# EC3micro.net
KiCad netlist of a schematic drawn in Altium Designer
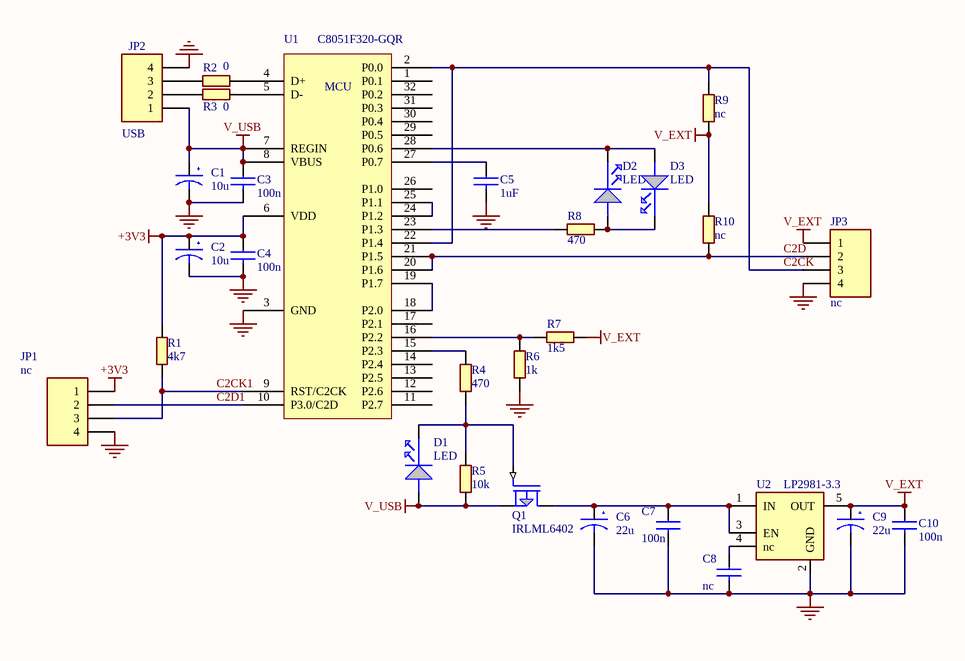
[diagram p0: EC3micro.SchDoc]

(export (version "E")
  (design (tool "Eeschema 10.0.6"))
  (components
    (comp (ref "C1") (value "10u") (footprint "TANTAL-A") (libsource (lib "RCS-Discret") (part "C-EL-TAN")))
    (comp (ref "C2") (value "10u") (footprint "TANTAL-A") (libsource (lib "RCS-Discret") (part "C-EL-TAN")))
    (comp (ref "C3") (value "100n") (footprint "C-0603") (libsource (lib "RCS-Discret") (part "C")))
    (comp (ref "C4") (value "100n") (footprint "C-0603") (libsource (lib "RCS-Discret") (part "C")))
    (comp (ref "C5") (value "1uF") (footprint "C-0805") (libsource (lib "RCS-Discret") (part "C")))
    (comp (ref "C6") (value "22u") (footprint "TANTAL-A") (libsource (lib "RCS-Discret") (part "C-EL-TAN")))
    (comp (ref "C7") (value "100n") (footprint "C-0603") (libsource (lib "RCS-Discret") (part "C")))
    (comp (ref "C8") (value "nc") (footprint "C-0603") (libsource (lib "RCS-Discret") (part "C")))
    (comp (ref "C9") (value "22u") (footprint "TANTAL-A") (libsource (lib "RCS-Discret") (part "C-EL-TAN")))
    (comp (ref "C10") (value "100n") (footprint "C-0603") (libsource (lib "RCS-Discret") (part "C")))
    (comp (ref "D1") (value "LED") (footprint "LED-0805") (libsource (lib "RCS-Discret") (part "LED")))
    (comp (ref "D2") (value "LED") (footprint "LED-0805") (libsource (lib "RCS-Discret") (part "LED")))
    (comp (ref "D3") (value "LED") (footprint "LED-0805") (libsource (lib "RCS-Discret") (part "LED")))
    (comp (ref "JP1")
      (value "nc")
      (footprint "IDS1-4P")
      (description "4 Pin Header 2,0 mm, 1x04")
      (libsource (lib "") (part "HEADER 4_1"))
    )
    (comp (ref "JP2")
      (value "USB")
      (footprint "CONN4_long")
      (description "4 Pin Header 2,0 mm, 1x04")
      (libsource (lib "e4") (part "HEADER 4"))
    )
    (comp (ref "JP3")
      (value "nc")
      (footprint "CONN4_long")
      (description "4 Pin Header 2,0 mm, 1x04")
      (libsource (lib "") (part "HEADER 4_2"))
    )
    (comp (ref "Q1")
      (value "IRLML6402")
      (footprint "SOT-23")
      (libsource (lib "RCS-Discret") (part "IRLML6402"))
    )
    (comp (ref "R1") (value "4k7") (footprint "R-0603") (libsource (lib "") (part "RES_1")))
    (comp (ref "R2") (value "0") (footprint "R-0603") (libsource (lib "e4") (part "RES")))
    (comp (ref "R3") (value "0") (footprint "R-0603") (libsource (lib "e4") (part "RES")))
    (comp (ref "R4") (value "470") (footprint "R-0603") (libsource (lib "") (part "RES_1")))
    (comp (ref "R5") (value "10k") (footprint "R-0603") (libsource (lib "") (part "RES_1")))
    (comp (ref "R6") (value "1k") (footprint "R-0603") (libsource (lib "") (part "RES_1")))
    (comp (ref "R7") (value "1k5") (footprint "R-0603") (libsource (lib "e4") (part "RES")))
    (comp (ref "R8") (value "470") (footprint "R-0603") (libsource (lib "e4") (part "RES")))
    (comp (ref "R9") (value "nc") (footprint "R-0603") (libsource (lib "") (part "RES_1")))
    (comp (ref "R10") (value "nc") (footprint "R-0603") (libsource (lib "") (part "RES_1")))
    (comp (ref "U1")
      (value "C8051F320-GQR")
      (footprint "QFP32")
      (libsource (lib "RCS-IMS") (part "C8051F320"))
    )
    (comp (ref "U2")
      (value "LP2981-3.3")
      (footprint "SOT-23-5")
      (libsource (lib "RCS-IMS") (part "LP2981-3.3"))
    )
  )
  (nets
    (net (code "1") (name "+3V3") (class "Default")
      (node (ref "C2") (pin "2") (pinfunction "+_2") (pintype "passive"))
      (node (ref "C4") (pin "1") (pinfunction "1_1") (pintype "passive"))
      (node (ref "JP1") (pin "1") (pinfunction "1_1") (pintype "passive"))
      (node (ref "R1") (pin "2") (pinfunction "2_2") (pintype "passive"))
      (node (ref "U1") (pin "6") (pinfunction "VDD_6") (pintype "passive"))
    )
    (net (code "2") (name "/C2CK") (class "Default")
      (node (ref "JP3") (pin "3") (pinfunction "3_3") (pintype "passive"))
      (node (ref "R9") (pin "2") (pinfunction "2_2") (pintype "passive"))
      (node (ref "U1") (pin "2") (pinfunction "P0.0_2") (pintype "passive"))
      (node (ref "U1") (pin "22") (pinfunction "P1.4_22") (pintype "passive"))
    )
    (net (code "3") (name "/C2CK1") (class "Default")
      (node (ref "JP1") (pin "3") (pinfunction "3_3") (pintype "passive"))
      (node (ref "R1") (pin "1") (pinfunction "1_1") (pintype "passive"))
      (node (ref "U1") (pin "9") (pinfunction "RST/C2CK_9") (pintype "passive"))
    )
    (net (code "4") (name "/C2D") (class "Default")
      (node (ref "JP3") (pin "2") (pinfunction "2_2") (pintype "passive"))
      (node (ref "R10") (pin "1") (pinfunction "1_1") (pintype "passive"))
      (node (ref "U1") (pin "20") (pinfunction "P1.6_20") (pintype "passive"))
      (node (ref "U1") (pin "21") (pinfunction "P1.5_21") (pintype "passive"))
    )
    (net (code "5") (name "/C2D1") (class "Default")
      (node (ref "JP1") (pin "2") (pinfunction "2_2") (pintype "passive"))
      (node (ref "U1") (pin "10") (pinfunction "P3.0/C2D_10") (pintype "passive"))
    )
    (net (code "6") (name "GND") (class "Default")
      (node (ref "C1") (pin "1") (pinfunction "-_1") (pintype "passive"))
      (node (ref "C10") (pin "2") (pinfunction "2_2") (pintype "passive"))
      (node (ref "C2") (pin "1") (pinfunction "-_1") (pintype "passive"))
      (node (ref "C3") (pin "2") (pinfunction "2_2") (pintype "passive"))
      (node (ref "C4") (pin "2") (pinfunction "2_2") (pintype "passive"))
      (node (ref "C5") (pin "2") (pinfunction "2_2") (pintype "passive"))
      (node (ref "C6") (pin "1") (pinfunction "-_1") (pintype "passive"))
      (node (ref "C7") (pin "2") (pinfunction "2_2") (pintype "passive"))
      (node (ref "C8") (pin "2") (pinfunction "2_2") (pintype "passive"))
      (node (ref "C9") (pin "1") (pinfunction "-_1") (pintype "passive"))
      (node (ref "JP1") (pin "4") (pinfunction "4_4") (pintype "passive"))
      (node (ref "JP2") (pin "4") (pinfunction "4_4") (pintype "passive"))
      (node (ref "JP3") (pin "4") (pinfunction "4_4") (pintype "passive"))
      (node (ref "R6") (pin "1") (pinfunction "1_1") (pintype "passive"))
      (node (ref "U1") (pin "3") (pinfunction "GND_3") (pintype "passive"))
      (node (ref "U2") (pin "2") (pinfunction "GND_2") (pintype "passive"))
    )
    (net (code "7") (name "Net-(C6-+)") (class "Default")
      (node (ref "C6") (pin "2") (pinfunction "+_2") (pintype "passive"))
      (node (ref "C7") (pin "1") (pinfunction "1_1") (pintype "passive"))
      (node (ref "Q1") (pin "2") (pinfunction "DRAIN_2") (pintype "passive"))
      (node (ref "U2") (pin "1") (pinfunction "IN_1") (pintype "passive"))
      (node (ref "U2") (pin "3") (pinfunction "EN_3") (pintype "passive"))
    )
    (net (code "8") (name "Net-(D1-CATHODE)") (class "Default")
      (node (ref "D1") (pin "K") (pinfunction "CATHODE_K") (pintype "passive"))
      (node (ref "Q1") (pin "1") (pinfunction "GATE_1") (pintype "input"))
      (node (ref "R4") (pin "1") (pinfunction "1_1") (pintype "passive"))
      (node (ref "R5") (pin "2") (pinfunction "2_2") (pintype "passive"))
    )
    (net (code "9") (name "Net-(D2-ANODE)") (class "Default")
      (node (ref "D2") (pin "A") (pinfunction "ANODE_A") (pintype "passive"))
      (node (ref "D3") (pin "K") (pinfunction "CATHODE_K") (pintype "passive"))
      (node (ref "R8") (pin "2") (pinfunction "2_2") (pintype "passive"))
    )
    (net (code "10") (name "Net-(D2-CATHODE)") (class "Default")
      (node (ref "D2") (pin "K") (pinfunction "CATHODE_K") (pintype "passive"))
      (node (ref "D3") (pin "A") (pinfunction "ANODE_A") (pintype "passive"))
      (node (ref "U1") (pin "28") (pinfunction "P0.6_28") (pintype "passive"))
    )
    (net (code "11") (name "Net-(JP2-Pad2)") (class "Default")
      (node (ref "JP2") (pin "2") (pinfunction "2_2") (pintype "passive"))
      (node (ref "R3") (pin "1") (pinfunction "1_1") (pintype "passive"))
    )
    (net (code "12") (name "Net-(JP2-Pad3)") (class "Default")
      (node (ref "JP2") (pin "3") (pinfunction "3_3") (pintype "passive"))
      (node (ref "R2") (pin "1") (pinfunction "1_1") (pintype "passive"))
    )
    (net (code "13") (name "Net-(U1-D+)") (class "Default")
      (node (ref "R2") (pin "2") (pinfunction "2_2") (pintype "passive"))
      (node (ref "U1") (pin "4") (pinfunction "D+_4") (pintype "passive"))
    )
    (net (code "14") (name "Net-(U1-D-)") (class "Default")
      (node (ref "R3") (pin "2") (pinfunction "2_2") (pintype "passive"))
      (node (ref "U1") (pin "5") (pinfunction "D-_5") (pintype "passive"))
    )
    (net (code "15") (name "Net-(U1-P0.7)") (class "Default")
      (node (ref "C5") (pin "1") (pinfunction "1_1") (pintype "passive"))
      (node (ref "U1") (pin "27") (pinfunction "P0.7_27") (pintype "passive"))
    )
    (net (code "16") (name "Net-(U1-P1.1)") (class "Default")
      (node (ref "U1") (pin "24") (pinfunction "P1.2_24") (pintype "passive"))
      (node (ref "U1") (pin "25") (pinfunction "P1.1_25") (pintype "passive"))
    )
    (net (code "17") (name "Net-(U1-P1.3)") (class "Default")
      (node (ref "R8") (pin "1") (pinfunction "1_1") (pintype "passive"))
      (node (ref "U1") (pin "23") (pinfunction "P1.3_23") (pintype "passive"))
    )
    (net (code "18") (name "Net-(U1-P1.7)") (class "Default")
      (node (ref "U1") (pin "18") (pinfunction "P2.0_18") (pintype "passive"))
      (node (ref "U1") (pin "19") (pinfunction "P1.7_19") (pintype "passive"))
    )
    (net (code "19") (name "Net-(U1-P2.2)") (class "Default")
      (node (ref "R6") (pin "2") (pinfunction "2_2") (pintype "passive"))
      (node (ref "R7") (pin "1") (pinfunction "1_1") (pintype "passive"))
      (node (ref "U1") (pin "16") (pinfunction "P2.2_16") (pintype "passive"))
    )
    (net (code "20") (name "Net-(U1-P2.3)") (class "Default")
      (node (ref "R4") (pin "2") (pinfunction "2_2") (pintype "passive"))
      (node (ref "U1") (pin "15") (pinfunction "P2.3_15") (pintype "passive"))
    )
    (net (code "21") (name "Net-(U2-nc)") (class "Default")
      (node (ref "C8") (pin "1") (pinfunction "1_1") (pintype "passive"))
      (node (ref "U2") (pin "4") (pinfunction "nc_4") (pintype "passive"))
    )
    (net (code "22") (name "V_EXT") (class "Default")
      (node (ref "C10") (pin "1") (pinfunction "1_1") (pintype "passive"))
      (node (ref "C9") (pin "2") (pinfunction "+_2") (pintype "passive"))
      (node (ref "JP3") (pin "1") (pinfunction "1_1") (pintype "passive"))
      (node (ref "R10") (pin "2") (pinfunction "2_2") (pintype "passive"))
      (node (ref "R7") (pin "2") (pinfunction "2_2") (pintype "passive"))
      (node (ref "R9") (pin "1") (pinfunction "1_1") (pintype "passive"))
      (node (ref "U2") (pin "5") (pinfunction "OUT_5") (pintype "passive"))
    )
    (net (code "23") (name "V_USB") (class "Default")
      (node (ref "C1") (pin "2") (pinfunction "+_2") (pintype "passive"))
      (node (ref "C3") (pin "1") (pinfunction "1_1") (pintype "passive"))
      (node (ref "D1") (pin "A") (pinfunction "ANODE_A") (pintype "passive"))
      (node (ref "JP2") (pin "1") (pinfunction "1_1") (pintype "passive"))
      (node (ref "Q1") (pin "3") (pinfunction "SOURCE_3") (pintype "passive"))
      (node (ref "R5") (pin "1") (pinfunction "1_1") (pintype "passive"))
      (node (ref "U1") (pin "7") (pinfunction "REGIN_7") (pintype "passive"))
      (node (ref "U1") (pin "8") (pinfunction "VBUS_8") (pintype "passive"))
    )
    (net (code "24") (name "unconnected-(U1-P0.1-Pad1)") (class "Default")
      (node (ref "U1") (pin "1") (pinfunction "P0.1_1") (pintype "passive"))
    )
    (net (code "25") (name "unconnected-(U1-P0.2-Pad32)") (class "Default")
      (node (ref "U1") (pin "32") (pinfunction "P0.2_32") (pintype "passive"))
    )
    (net (code "26") (name "unconnected-(U1-P0.3-Pad31)") (class "Default")
      (node (ref "U1") (pin "31") (pinfunction "P0.3_31") (pintype "passive"))
    )
    (net (code "27") (name "unconnected-(U1-P0.4-Pad30)") (class "Default")
      (node (ref "U1") (pin "30") (pinfunction "P0.4_30") (pintype "passive"))
    )
    (net (code "28") (name "unconnected-(U1-P0.5-Pad29)") (class "Default")
      (node (ref "U1") (pin "29") (pinfunction "P0.5_29") (pintype "passive"))
    )
    (net (code "29") (name "unconnected-(U1-P1.0-Pad26)") (class "Default")
      (node (ref "U1") (pin "26") (pinfunction "P1.0_26") (pintype "passive"))
    )
    (net (code "30") (name "unconnected-(U1-P2.1-Pad17)") (class "Default")
      (node (ref "U1") (pin "17") (pinfunction "P2.1_17") (pintype "passive"))
    )
    (net (code "31") (name "unconnected-(U1-P2.4-Pad14)") (class "Default")
      (node (ref "U1") (pin "14") (pinfunction "P2.4_14") (pintype "passive"))
    )
    (net (code "32") (name "unconnected-(U1-P2.5-Pad13)") (class "Default")
      (node (ref "U1") (pin "13") (pinfunction "P2.5_13") (pintype "passive"))
    )
    (net (code "33") (name "unconnected-(U1-P2.6-Pad12)") (class "Default")
      (node (ref "U1") (pin "12") (pinfunction "P2.6_12") (pintype "passive"))
    )
    (net (code "34") (name "unconnected-(U1-P2.7-Pad11)") (class "Default")
      (node (ref "U1") (pin "11") (pinfunction "P2.7_11") (pintype "passive"))
    )
  )
)
